# board.net
KiCad netlist of a schematic drawn in EAGLE
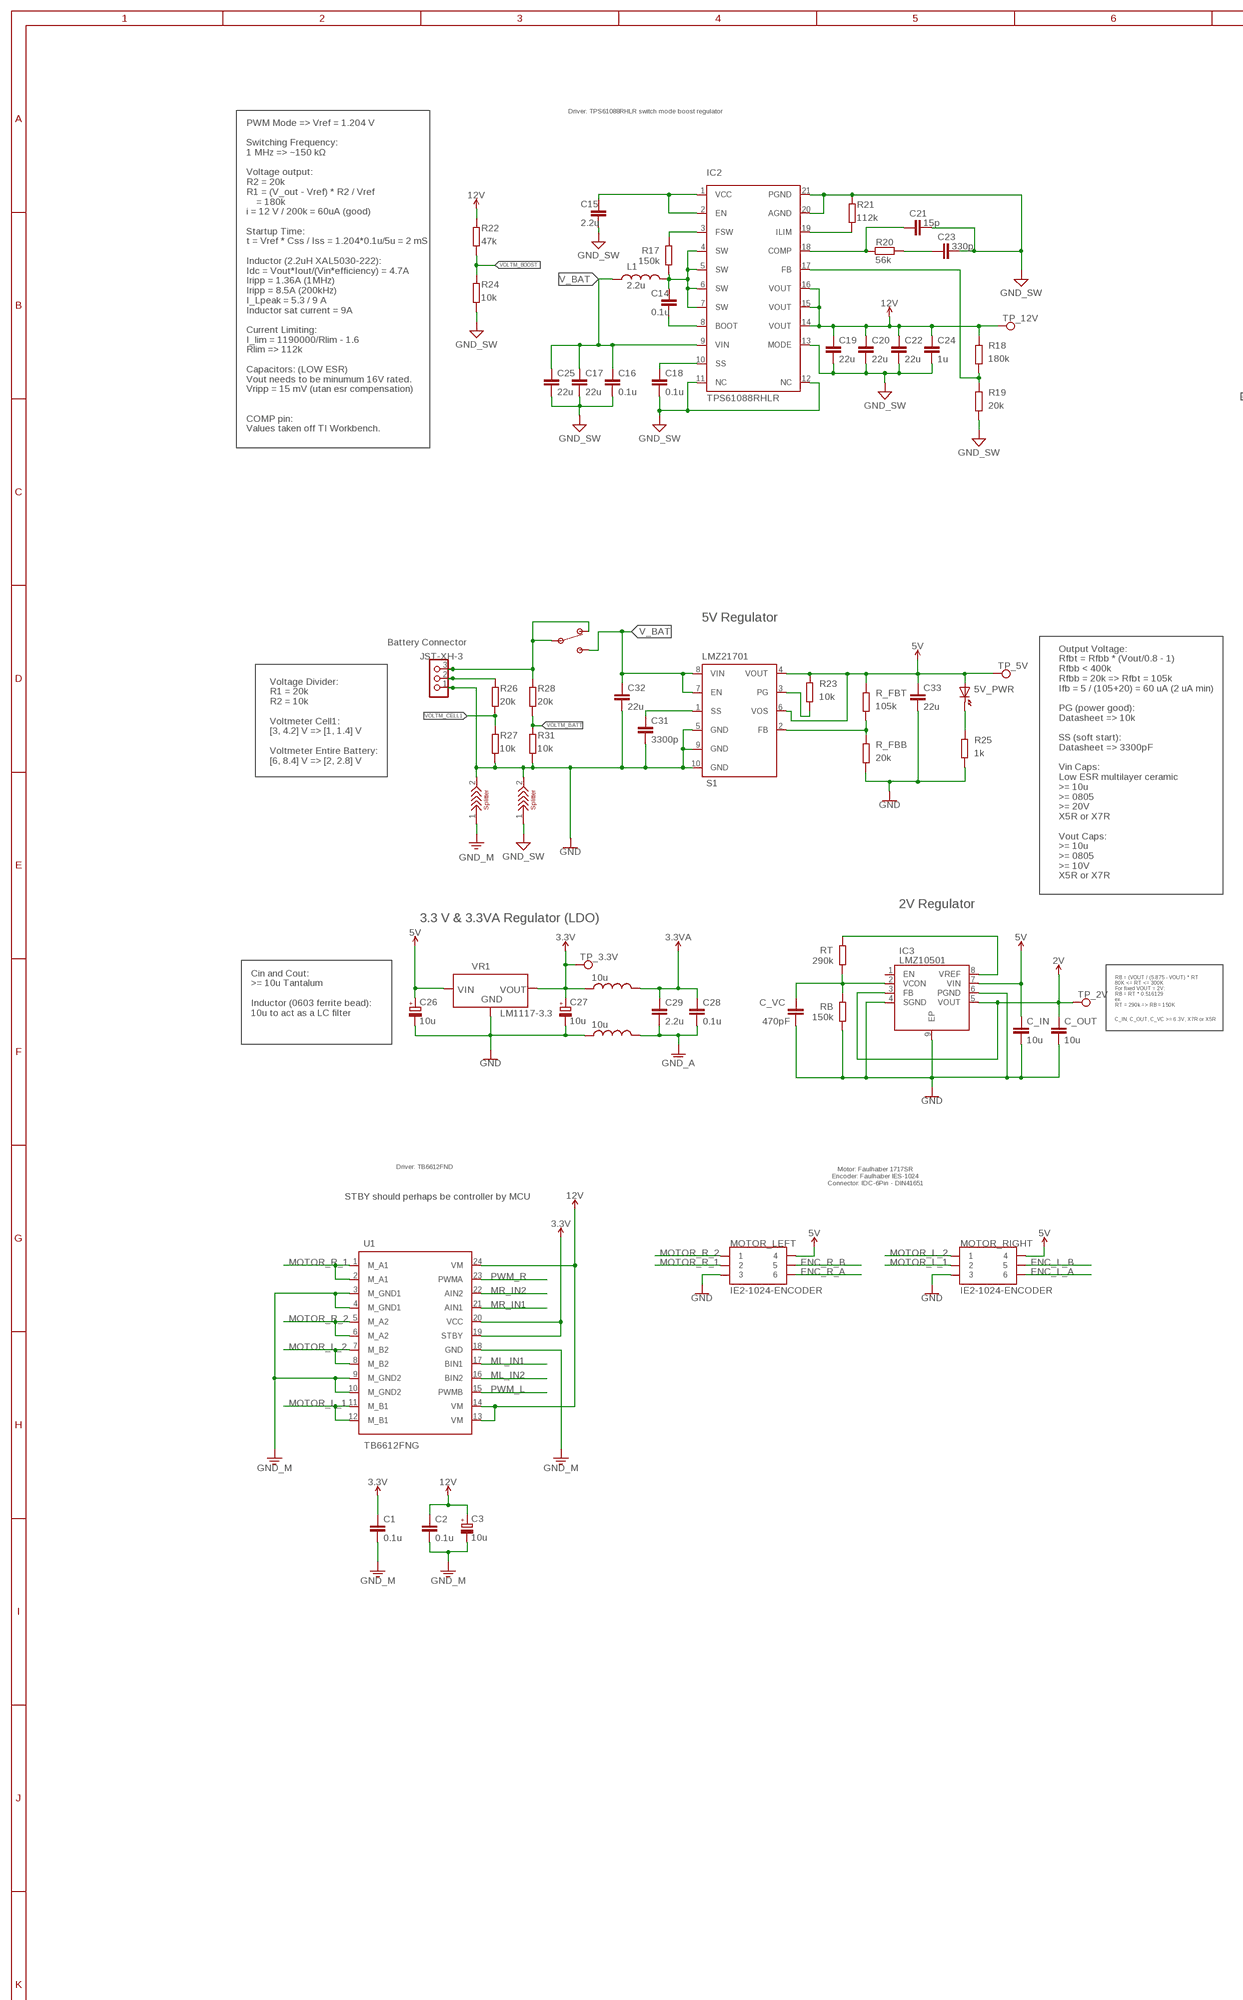
[diagram p0: schematic, sheet 1, part 1 of 3]
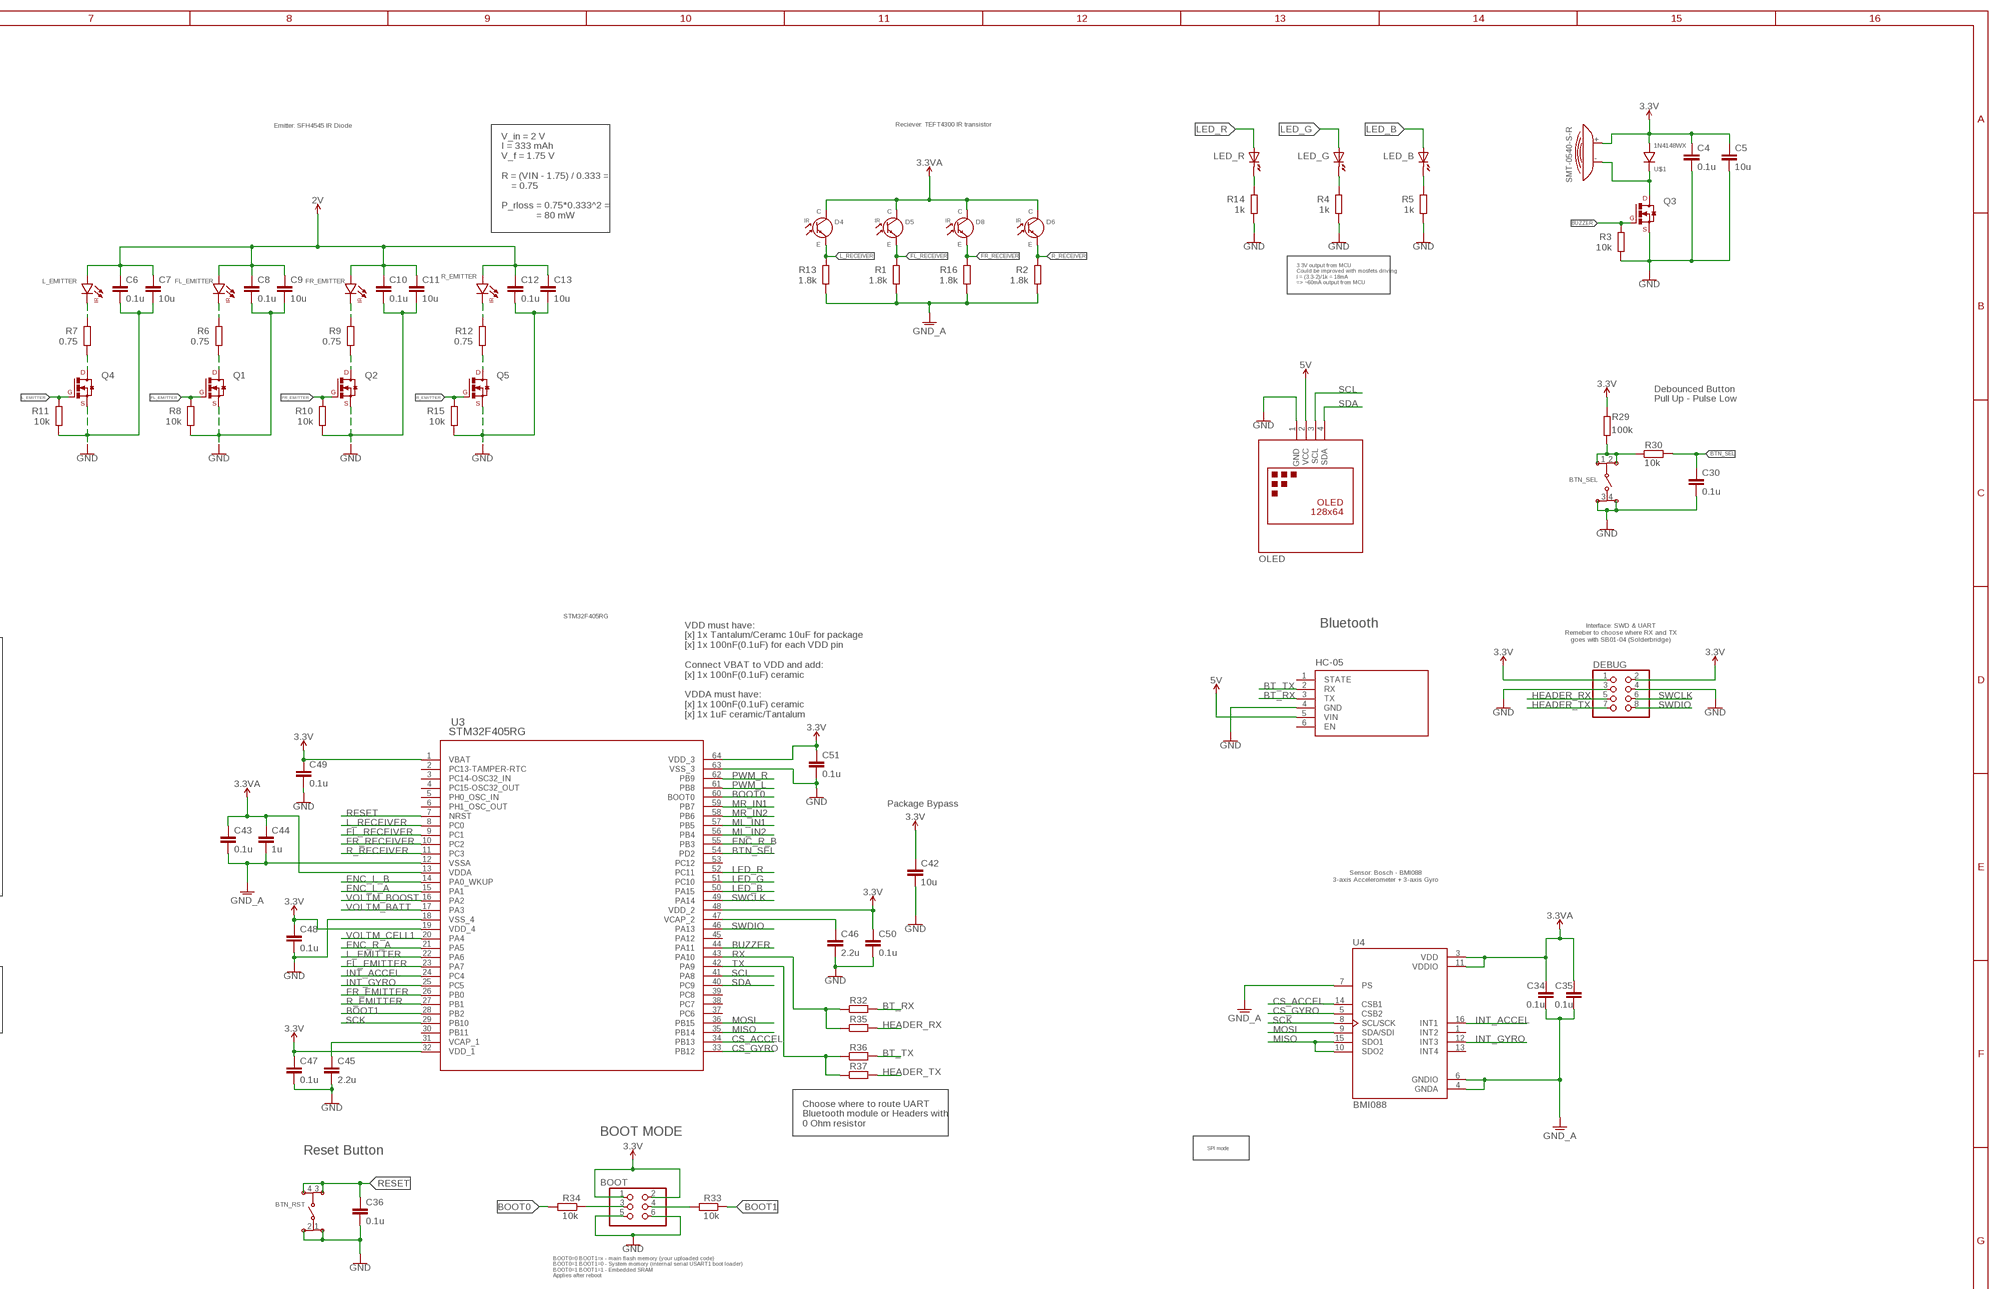
[diagram p1: schematic, sheet 1, part 2 of 3]
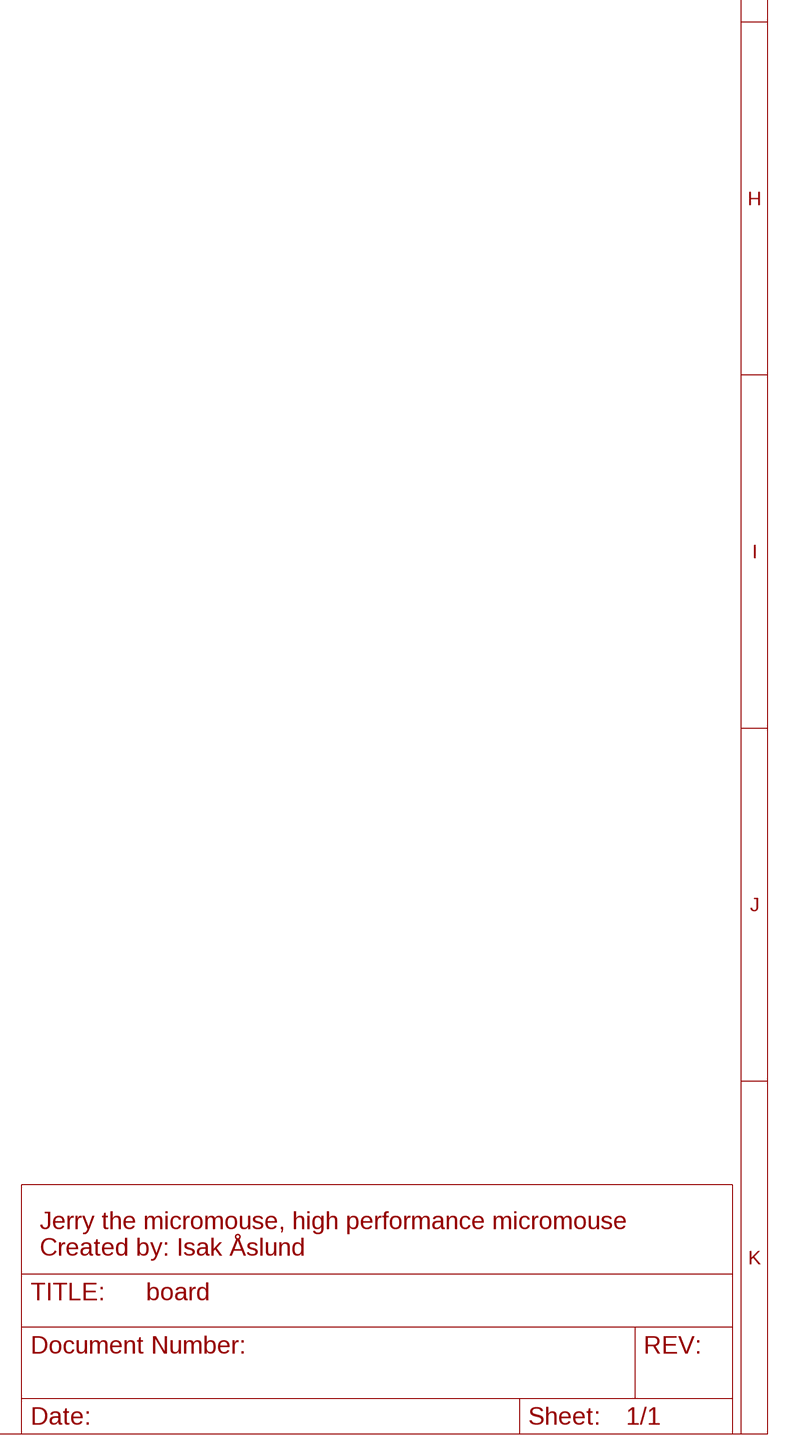
[diagram p2: schematic, sheet 1, part 3 of 3]

(export (version "E")
  (design (tool "Eeschema 10.0.6"))
  (components
    (comp (ref "5V_PWR")
      (value "CHIP-LED0603")
      (footprint "eagle-import:CHIP-LED0603")
      (libsource (lib "eagle-import") (part "CHIP-LED0603"))
    )
    (comp (ref "BOOT")
      (value "PINHD-2X3")
      (footprint "eagle-import:2X03")
      (libsource (lib "eagle-import") (part "PINHD-2X3"))
    )
    (comp (ref "BTN_RST")
      (value "KMR621NGLFS")
      (footprint "eagle-import:KMR621NGLFS")
      (libsource (lib "eagle-import") (part "KMR621NGLFS"))
    )
    (comp (ref "BTN_SEL")
      (value "KMR621NGLFS")
      (footprint "eagle-import:KMR621NGLFS")
      (libsource (lib "eagle-import") (part "KMR621NGLFS"))
    )
    (comp (ref "C1")
      (value "0.1u")
      (footprint "eagle-import:C0603")
      (libsource (lib "eagle-import") (part "C0603"))
    )
    (comp (ref "C2")
      (value "0.1u")
      (footprint "eagle-import:C0603")
      (libsource (lib "eagle-import") (part "C0603"))
    )
    (comp (ref "C3")
      (value "10u")
      (footprint "eagle-import:EIA_6032-28")
      (libsource (lib "eagle-import") (part "KEMET_C"))
    )
    (comp (ref "C4")
      (value "0.1u")
      (footprint "eagle-import:C0603")
      (libsource (lib "eagle-import") (part "C0603"))
    )
    (comp (ref "C5")
      (value "10u")
      (footprint "eagle-import:C0603")
      (libsource (lib "eagle-import") (part "C0603"))
    )
    (comp (ref "C6")
      (value "0.1u")
      (footprint "eagle-import:C0603")
      (libsource (lib "eagle-import") (part "C0603"))
    )
    (comp (ref "C7")
      (value "10u")
      (footprint "eagle-import:C0603")
      (libsource (lib "eagle-import") (part "C0603"))
    )
    (comp (ref "C8")
      (value "0.1u")
      (footprint "eagle-import:C0603")
      (libsource (lib "eagle-import") (part "C0603"))
    )
    (comp (ref "C9")
      (value "10u")
      (footprint "eagle-import:C0603")
      (libsource (lib "eagle-import") (part "C0603"))
    )
    (comp (ref "C10")
      (value "0.1u")
      (footprint "eagle-import:C0603")
      (libsource (lib "eagle-import") (part "C0603"))
    )
    (comp (ref "C11")
      (value "10u")
      (footprint "eagle-import:C0603")
      (libsource (lib "eagle-import") (part "C0603"))
    )
    (comp (ref "C12")
      (value "0.1u")
      (footprint "eagle-import:C0603")
      (libsource (lib "eagle-import") (part "C0603"))
    )
    (comp (ref "C13")
      (value "10u")
      (footprint "eagle-import:C0603")
      (libsource (lib "eagle-import") (part "C0603"))
    )
    (comp (ref "C14")
      (value "0.1u")
      (footprint "eagle-import:C0603")
      (libsource (lib "eagle-import") (part "C0603"))
    )
    (comp (ref "C15")
      (value "2.2u")
      (footprint "eagle-import:C0603")
      (libsource (lib "eagle-import") (part "C0603"))
    )
    (comp (ref "C16")
      (value "0.1u")
      (footprint "eagle-import:C0805")
      (libsource (lib "eagle-import") (part "C0805"))
    )
    (comp (ref "C17")
      (value "22u")
      (footprint "eagle-import:C0805")
      (libsource (lib "eagle-import") (part "C0805"))
    )
    (comp (ref "C18")
      (value "0.1u")
      (footprint "eagle-import:C0603")
      (libsource (lib "eagle-import") (part "C0603"))
    )
    (comp (ref "C19")
      (value "22u")
      (footprint "eagle-import:C0805")
      (libsource (lib "eagle-import") (part "C0805"))
    )
    (comp (ref "C20")
      (value "22u")
      (footprint "eagle-import:C0805")
      (libsource (lib "eagle-import") (part "C0805"))
    )
    (comp (ref "C21")
      (value "15p")
      (footprint "eagle-import:C0603")
      (libsource (lib "eagle-import") (part "C0603"))
    )
    (comp (ref "C22")
      (value "22u")
      (footprint "eagle-import:C0805")
      (libsource (lib "eagle-import") (part "C0805"))
    )
    (comp (ref "C23")
      (value "330p")
      (footprint "eagle-import:C0603")
      (libsource (lib "eagle-import") (part "C0603"))
    )
    (comp (ref "C24")
      (value "1u")
      (footprint "eagle-import:C0805")
      (libsource (lib "eagle-import") (part "C0805"))
    )
    (comp (ref "C25")
      (value "22u")
      (footprint "eagle-import:C0805")
      (libsource (lib "eagle-import") (part "C0805"))
    )
    (comp (ref "C26")
      (value "10u")
      (footprint "eagle-import:SMC_A")
      (libsource (lib "eagle-import") (part "SMC_A"))
    )
    (comp (ref "C27")
      (value "10u")
      (footprint "eagle-import:SMC_A")
      (libsource (lib "eagle-import") (part "SMC_A"))
    )
    (comp (ref "C28")
      (value "0.1u")
      (footprint "eagle-import:C0603")
      (libsource (lib "eagle-import") (part "C0603"))
    )
    (comp (ref "C29")
      (value "2.2u")
      (footprint "eagle-import:C0603")
      (libsource (lib "eagle-import") (part "C0603"))
    )
    (comp (ref "C30")
      (value "0.1u")
      (footprint "eagle-import:C0603")
      (libsource (lib "eagle-import") (part "C0603"))
    )
    (comp (ref "C31")
      (value "3300p")
      (footprint "eagle-import:C0603")
      (libsource (lib "eagle-import") (part "C0603"))
    )
    (comp (ref "C32")
      (value "22u")
      (footprint "eagle-import:C0805")
      (libsource (lib "eagle-import") (part "C0805"))
    )
    (comp (ref "C33")
      (value "22u")
      (footprint "eagle-import:C0805")
      (libsource (lib "eagle-import") (part "C0805"))
    )
    (comp (ref "C34")
      (value "0.1u")
      (footprint "eagle-import:C0603")
      (libsource (lib "eagle-import") (part "C0603"))
    )
    (comp (ref "C35")
      (value "0.1u")
      (footprint "eagle-import:C0603")
      (libsource (lib "eagle-import") (part "C0603"))
    )
    (comp (ref "C36")
      (value "0.1u")
      (footprint "eagle-import:C0603")
      (libsource (lib "eagle-import") (part "C0603"))
    )
    (comp (ref "C42")
      (value "10u")
      (footprint "eagle-import:C0603")
      (libsource (lib "eagle-import") (part "C0603"))
    )
    (comp (ref "C43")
      (value "0.1u")
      (footprint "eagle-import:C0603")
      (libsource (lib "eagle-import") (part "C0603"))
    )
    (comp (ref "C44")
      (value "1u")
      (footprint "eagle-import:C0603")
      (libsource (lib "eagle-import") (part "C0603"))
    )
    (comp (ref "C45")
      (value "2.2u")
      (footprint "eagle-import:C0603")
      (libsource (lib "eagle-import") (part "C0603"))
    )
    (comp (ref "C46")
      (value "2.2u")
      (footprint "eagle-import:C0603")
      (libsource (lib "eagle-import") (part "C0603"))
    )
    (comp (ref "C47")
      (value "0.1u")
      (footprint "eagle-import:C0603")
      (libsource (lib "eagle-import") (part "C0603"))
    )
    (comp (ref "C48")
      (value "0.1u")
      (footprint "eagle-import:C0603")
      (libsource (lib "eagle-import") (part "C0603"))
    )
    (comp (ref "C49")
      (value "0.1u")
      (footprint "eagle-import:C0603")
      (libsource (lib "eagle-import") (part "C0603"))
    )
    (comp (ref "C50")
      (value "0.1u")
      (footprint "eagle-import:C0603")
      (libsource (lib "eagle-import") (part "C0603"))
    )
    (comp (ref "C51")
      (value "0.1u")
      (footprint "eagle-import:C0603")
      (libsource (lib "eagle-import") (part "C0603"))
    )
    (comp (ref "C_IN")
      (value "10u")
      (footprint "eagle-import:C0805")
      (libsource (lib "eagle-import") (part "C0805"))
    )
    (comp (ref "C_OUT")
      (value "10u")
      (footprint "eagle-import:C0805")
      (libsource (lib "eagle-import") (part "C0805"))
    )
    (comp (ref "C_VC")
      (value "470pF")
      (footprint "eagle-import:C0603")
      (libsource (lib "eagle-import") (part "C0603"))
    )
    (comp (ref "D4")
      (value "TEFT4300")
      (footprint "eagle-import:3MM_PHOTOTRANSISTOR")
      (libsource (lib "eagle-import") (part "TEFT4300"))
    )
    (comp (ref "D5")
      (value "TEFT4300")
      (footprint "eagle-import:3MM_PHOTOTRANSISTOR")
      (libsource (lib "eagle-import") (part "TEFT4300"))
    )
    (comp (ref "D6")
      (value "TEFT4300")
      (footprint "eagle-import:3MM_PHOTOTRANSISTOR")
      (libsource (lib "eagle-import") (part "TEFT4300"))
    )
    (comp (ref "D8")
      (value "TEFT4300")
      (footprint "eagle-import:3MM_PHOTOTRANSISTOR")
      (libsource (lib "eagle-import") (part "TEFT4300"))
    )
    (comp (ref "DEBUG")
      (value "PINHD-2X4")
      (footprint "eagle-import:2X04")
      (libsource (lib "eagle-import") (part "PINHD-2X4"))
    )
    (comp (ref "FL_EMITTER")
      (value "SFH_4545")
      (footprint "eagle-import:SFH_4545")
      (libsource (lib "eagle-import") (part "SFH_4545"))
    )
    (comp (ref "FP1")
      (value "10u")
      (footprint "eagle-import:R0805")
      (libsource (lib "eagle-import") (part "WE-CBF_0805"))
    )
    (comp (ref "FP2")
      (value "10u")
      (footprint "eagle-import:R0805")
      (libsource (lib "eagle-import") (part "WE-CBF_0805"))
    )
    (comp (ref "FR_EMITTER")
      (value "SFH_4545")
      (footprint "eagle-import:SFH_4545")
      (libsource (lib "eagle-import") (part "SFH_4545"))
    )
    (comp (ref "HC-05")
      (value "WIRELESS-BLUETOOTH-HC-05")
      (footprint "eagle-import:WIRELESS-BLUETOOTH-HC-05")
      (libsource (lib "eagle-import") (part "WIRELESS-BLUETOOTH-HC-05"))
    )
    (comp (ref "IC2")
      (value "TPS61088RHLR")
      (footprint "eagle-import:RHL(R-PVQFN-N20)_1")
      (fields (field (name "MOUSER_PART_NUMBER") "595-TPS61088RHLR"))
      (libsource (lib "eagle-import") (part "TPS61088RHLR"))
    )
    (comp (ref "IC3")
      (value "LMZ10501")
      (footprint "eagle-import:SON65P260X300X150-9N")
      (fields
        (field (name "MANUFACTURER_PART_NUMBER") "LMZ10501SILT")
        (field (name "MOUSER_PART_NUMBER") "595-LMZ10501SILT")
      )
      (libsource (lib "eagle-import") (part "LMZ10501"))
    )
    (comp (ref "L1")
      (value "2.2u")
      (footprint "eagle-import:XAL5030")
      (fields
        (field (name "MANUFACTURER_PART_NUMBER") "XAL5030-222MEC")
        (field (name "MOUSER_PART_NUMBER") "994-XAL5030-222MEC")
      )
      (libsource (lib "eagle-import") (part "XAL5030-222MEC"))
    )
    (comp (ref "LED_B")
      (value "CHIP-LED0603")
      (footprint "eagle-import:CHIP-LED0603")
      (libsource (lib "eagle-import") (part "CHIP-LED0603"))
    )
    (comp (ref "LED_G")
      (value "CHIP-LED0603")
      (footprint "eagle-import:CHIP-LED0603")
      (libsource (lib "eagle-import") (part "CHIP-LED0603"))
    )
    (comp (ref "LED_R")
      (value "CHIP-LED0603")
      (footprint "eagle-import:CHIP-LED0603")
      (libsource (lib "eagle-import") (part "CHIP-LED0603"))
    )
    (comp (ref "L_EMITTER")
      (value "SFH_4545")
      (footprint "eagle-import:SFH_4545")
      (libsource (lib "eagle-import") (part "SFH_4545"))
    )
    (comp (ref "MOTOR_LEFT")
      (value "IE2-1024-ENCODER")
      (footprint "eagle-import:IE2-1024-ENCODER")
      (libsource (lib "eagle-import") (part "IE2-1024-ENCODER"))
    )
    (comp (ref "MOTOR_RIGHT")
      (value "IE2-1024-ENCODER")
      (footprint "eagle-import:IE2-1024-ENCODER")
      (libsource (lib "eagle-import") (part "IE2-1024-ENCODER"))
    )
    (comp (ref "OLED")
      (value "DISPLAY-OLED-128X64-I2C")
      (footprint "eagle-import:DISPLAY-OLED-128X64-I2C")
      (libsource (lib "eagle-import") (part "DISPLAY-OLED-128X64-I2C"))
    )
    (comp (ref "Q1")
      (value "IRFML8244TRPBF")
      (footprint "eagle-import:SOT95P235X110-3")
      (libsource (lib "eagle-import") (part "IRFML8244TRPBF"))
    )
    (comp (ref "Q2")
      (value "IRFML8244TRPBF")
      (footprint "eagle-import:SOT95P235X110-3")
      (libsource (lib "eagle-import") (part "IRFML8244TRPBF"))
    )
    (comp (ref "Q3")
      (value "IRFML8244TRPBF")
      (footprint "eagle-import:SOT95P235X110-3")
      (libsource (lib "eagle-import") (part "IRFML8244TRPBF"))
    )
    (comp (ref "Q4")
      (value "IRFML8244TRPBF")
      (footprint "eagle-import:SOT95P235X110-3")
      (libsource (lib "eagle-import") (part "IRFML8244TRPBF"))
    )
    (comp (ref "Q5")
      (value "IRFML8244TRPBF")
      (footprint "eagle-import:SOT95P235X110-3")
      (libsource (lib "eagle-import") (part "IRFML8244TRPBF"))
    )
    (comp (ref "R1")
      (value "1.8k")
      (footprint "eagle-import:R0603")
      (libsource (lib "eagle-import") (part "R0603"))
    )
    (comp (ref "R2")
      (value "1.8k")
      (footprint "eagle-import:R0603")
      (libsource (lib "eagle-import") (part "R0603"))
    )
    (comp (ref "R3")
      (value "10k")
      (footprint "eagle-import:R0603")
      (libsource (lib "eagle-import") (part "R0603"))
    )
    (comp (ref "R4")
      (value "1k")
      (footprint "eagle-import:R0603")
      (libsource (lib "eagle-import") (part "R0603"))
    )
    (comp (ref "R5")
      (value "1k")
      (footprint "eagle-import:R0603")
      (libsource (lib "eagle-import") (part "R0603"))
    )
    (comp (ref "R6")
      (value "0.75")
      (footprint "eagle-import:R0603")
      (libsource (lib "eagle-import") (part "R0603"))
    )
    (comp (ref "R7")
      (value "0.75")
      (footprint "eagle-import:R0603")
      (libsource (lib "eagle-import") (part "R0603"))
    )
    (comp (ref "R8")
      (value "10k")
      (footprint "eagle-import:R0603")
      (libsource (lib "eagle-import") (part "R0603"))
    )
    (comp (ref "R9")
      (value "0.75")
      (footprint "eagle-import:R0603")
      (libsource (lib "eagle-import") (part "R0603"))
    )
    (comp (ref "R10")
      (value "10k")
      (footprint "eagle-import:R0603")
      (libsource (lib "eagle-import") (part "R0603"))
    )
    (comp (ref "R11")
      (value "10k")
      (footprint "eagle-import:R0603")
      (libsource (lib "eagle-import") (part "R0603"))
    )
    (comp (ref "R12")
      (value "0.75")
      (footprint "eagle-import:R0603")
      (libsource (lib "eagle-import") (part "R0603"))
    )
    (comp (ref "R13")
      (value "1.8k")
      (footprint "eagle-import:R0603")
      (libsource (lib "eagle-import") (part "R0603"))
    )
    (comp (ref "R14")
      (value "1k")
      (footprint "eagle-import:R0603")
      (libsource (lib "eagle-import") (part "R0603"))
    )
    (comp (ref "R15")
      (value "10k")
      (footprint "eagle-import:R0603")
      (libsource (lib "eagle-import") (part "R0603"))
    )
    (comp (ref "R16")
      (value "1.8k")
      (footprint "eagle-import:R0603")
      (libsource (lib "eagle-import") (part "R0603"))
    )
    (comp (ref "R17")
      (value "150k")
      (footprint "eagle-import:R0603")
      (libsource (lib "eagle-import") (part "R0603"))
    )
    (comp (ref "R18")
      (value "180k")
      (footprint "eagle-import:R0603")
      (libsource (lib "eagle-import") (part "R0603"))
    )
    (comp (ref "R19")
      (value "20k")
      (footprint "eagle-import:R0603")
      (libsource (lib "eagle-import") (part "R0603"))
    )
    (comp (ref "R20")
      (value "56k")
      (footprint "eagle-import:R0603")
      (libsource (lib "eagle-import") (part "R0603"))
    )
    (comp (ref "R21")
      (value "112k")
      (footprint "eagle-import:R0603")
      (libsource (lib "eagle-import") (part "R0603"))
    )
    (comp (ref "R22")
      (value "47k")
      (footprint "eagle-import:R0603")
      (libsource (lib "eagle-import") (part "R0603"))
    )
    (comp (ref "R23")
      (value "10k")
      (footprint "eagle-import:R0603")
      (fields (field (name "TOLERANCE") "1%"))
      (libsource (lib "eagle-import") (part "R0603"))
    )
    (comp (ref "R24")
      (value "10k")
      (footprint "eagle-import:R0603")
      (libsource (lib "eagle-import") (part "R0603"))
    )
    (comp (ref "R25")
      (value "1k")
      (footprint "eagle-import:R0603")
      (libsource (lib "eagle-import") (part "R0603"))
    )
    (comp (ref "R26")
      (value "20k")
      (footprint "eagle-import:R0603")
      (libsource (lib "eagle-import") (part "R0603"))
    )
    (comp (ref "R27")
      (value "10k")
      (footprint "eagle-import:R0603")
      (libsource (lib "eagle-import") (part "R0603"))
    )
    (comp (ref "R28")
      (value "20k")
      (footprint "eagle-import:R0603")
      (libsource (lib "eagle-import") (part "R0603"))
    )
    (comp (ref "R29")
      (value "100k")
      (footprint "eagle-import:R0603")
      (libsource (lib "eagle-import") (part "R0603"))
    )
    (comp (ref "R30")
      (value "10k")
      (footprint "eagle-import:R0603")
      (libsource (lib "eagle-import") (part "R0603"))
    )
    (comp (ref "R31")
      (value "10k")
      (footprint "eagle-import:R0603")
      (libsource (lib "eagle-import") (part "R0603"))
    )
    (comp (ref "R32")
      (value "0")
      (footprint "eagle-import:R0603")
      (libsource (lib "eagle-import") (part "R0603"))
    )
    (comp (ref "R33")
      (value "10k")
      (footprint "eagle-import:R0603")
      (libsource (lib "eagle-import") (part "R0603"))
    )
    (comp (ref "R34")
      (value "10k")
      (footprint "eagle-import:R0603")
      (libsource (lib "eagle-import") (part "R0603"))
    )
    (comp (ref "R35")
      (value "0")
      (footprint "eagle-import:R0603")
      (libsource (lib "eagle-import") (part "R0603"))
    )
    (comp (ref "R36")
      (value "0")
      (footprint "eagle-import:R0603")
      (libsource (lib "eagle-import") (part "R0603"))
    )
    (comp (ref "R37")
      (value "0")
      (footprint "eagle-import:R0603")
      (libsource (lib "eagle-import") (part "R0603"))
    )
    (comp (ref "RB")
      (value "150k")
      (footprint "eagle-import:R0603")
      (libsource (lib "eagle-import") (part "R0603"))
    )
    (comp (ref "RT")
      (value "290k")
      (footprint "eagle-import:R0603")
      (fields (field (name "TOLERANCE") "1%"))
      (libsource (lib "eagle-import") (part "R0603"))
    )
    (comp (ref "R_EMITTER")
      (value "SFH_4545")
      (footprint "eagle-import:SFH_4545")
      (libsource (lib "eagle-import") (part "SFH_4545"))
    )
    (comp (ref "R_FBB")
      (value "20k")
      (footprint "eagle-import:R0603")
      (libsource (lib "eagle-import") (part "R0603"))
    )
    (comp (ref "R_FBT")
      (value "105k")
      (footprint "eagle-import:R0603")
      (libsource (lib "eagle-import") (part "R0603"))
    )
    (comp (ref "S1")
      (value "LMZ21701")
      (footprint "eagle-import:LMZ21701")
      (fields
        (field (name "MANUFACTURER_PART_NUMBER") "LMZ21701SILR")
        (field (name "MOUSER_PART_NUMBER") "595-LMZ21701SILR")
      )
      (libsource (lib "eagle-import") (part "LMZ21701"))
    )
    (comp (ref "SW")
      (value "SPDT-500SSP1S1M6QEA")
      (footprint "eagle-import:500SSP1S1M6QEA")
      (libsource (lib "eagle-import") (part "SPDT-500SSP1S1M6QEA"))
    )
    (comp (ref "TP_2V")
      (value "TEST-POINT3X5")
      (footprint "eagle-import:PAD.03X.05")
      (libsource (lib "eagle-import") (part "TEST-POINT3X5"))
    )
    (comp (ref "TP_3.3V")
      (value "TEST-POINT3X5")
      (footprint "eagle-import:PAD.03X.05")
      (libsource (lib "eagle-import") (part "TEST-POINT3X5"))
    )
    (comp (ref "TP_5V")
      (value "TEST-POINT3X5")
      (footprint "eagle-import:PAD.03X.05")
      (libsource (lib "eagle-import") (part "TEST-POINT3X5"))
    )
    (comp (ref "TP_12V")
      (value "TEST-POINT3X5")
      (footprint "eagle-import:PAD.03X.05")
      (libsource (lib "eagle-import") (part "TEST-POINT3X5"))
    )
    (comp (ref "U$1")
      (value "1N4148WX")
      (footprint "eagle-import:1N4148WX_SOD-323-2")
      (libsource (lib "eagle-import") (part "DIODE_1N4148WX"))
    )
    (comp (ref "U$4")
      (value "SMT-0540-S-R")
      (footprint "eagle-import:SMT-0540-S-R")
      (libsource (lib "eagle-import") (part "SMT-0540-S-R"))
    )
    (comp (ref "U$6")
      (value "SPLITTER")
      (footprint "eagle-import:SPLITTER")
      (libsource (lib "eagle-import") (part "SPLITTER"))
    )
    (comp (ref "U$7")
      (value "SPLITTER")
      (footprint "eagle-import:SPLITTER")
      (libsource (lib "eagle-import") (part "SPLITTER"))
    )
    (comp (ref "U$10")
      (value "JST-XH-3")
      (footprint "eagle-import:JST-XH-03")
      (libsource (lib "eagle-import") (part "JST-XH-3"))
    )
    (comp (ref "U1")
      (value "TB6612FNG")
      (footprint "eagle-import:SOP65P760X160-24")
      (libsource (lib "eagle-import") (part "TB6612FNG"))
    )
    (comp (ref "U3")
      (value "STM32F405RG")
      (footprint "eagle-import:LQFP-64")
      (libsource (lib "eagle-import") (part "STM32F405RG"))
    )
    (comp (ref "U4")
      (value "BMI088")
      (footprint "eagle-import:PQFN50P450X300X100-16N")
      (fields (field (name "MF") "Bosch Sensortec"))
      (libsource (lib "eagle-import") (part "BMI088"))
    )
    (comp (ref "VR1")
      (value "LM1117-3.3")
      (footprint "eagle-import:SOT230P700X180-4")
      (libsource (lib "eagle-import") (part "LM1117-3.3"))
    )
  )
  (nets
    (net (code "1") (name "/BT_RX") (class "Default")
      (node (ref "HC-05") (pin "3") (pinfunction "TX_3") (pintype "output"))
      (node (ref "R32") (pin "2") (pinfunction "2_2") (pintype "passive"))
    )
    (net (code "2") (name "/BT_TX") (class "Default")
      (node (ref "HC-05") (pin "2") (pinfunction "RX_2") (pintype "input"))
      (node (ref "R36") (pin "2") (pinfunction "2_2") (pintype "passive"))
    )
    (net (code "3") (name "/CS_ACCEL") (class "Default")
      (node (ref "U3") (pin "34") (pinfunction "PB13_34") (pintype "bidirectional"))
      (node (ref "U4") (pin "14") (pinfunction "CSB1_14") (pintype "input"))
    )
    (net (code "4") (name "/CS_GYRO") (class "Default")
      (node (ref "U3") (pin "33") (pinfunction "PB12_33") (pintype "bidirectional"))
      (node (ref "U4") (pin "5") (pinfunction "CSB2_5") (pintype "input"))
    )
    (net (code "5") (name "/ENC_L_A") (class "Default")
      (node (ref "MOTOR_RIGHT") (pin "6") (pinfunction "6_6") (pintype "bidirectional"))
      (node (ref "U3") (pin "15") (pinfunction "PA1_15") (pintype "bidirectional"))
    )
    (net (code "6") (name "/ENC_L_B") (class "Default")
      (node (ref "MOTOR_RIGHT") (pin "5") (pinfunction "5_5") (pintype "bidirectional"))
      (node (ref "U3") (pin "14") (pinfunction "PA0_WKUP_14") (pintype "bidirectional"))
    )
    (net (code "7") (name "/ENC_R_A") (class "Default")
      (node (ref "MOTOR_LEFT") (pin "6") (pinfunction "6_6") (pintype "bidirectional"))
      (node (ref "U3") (pin "21") (pinfunction "PA5_21") (pintype "bidirectional"))
    )
    (net (code "8") (name "/ENC_R_B") (class "Default")
      (node (ref "MOTOR_LEFT") (pin "5") (pinfunction "5_5") (pintype "bidirectional"))
      (node (ref "U3") (pin "55") (pinfunction "PB3_55") (pintype "bidirectional"))
    )
    (net (code "9") (name "/HEADER_RX") (class "Default")
      (node (ref "DEBUG") (pin "5") (pinfunction "5_5") (pintype "passive"))
      (node (ref "R35") (pin "2") (pinfunction "2_2") (pintype "passive"))
    )
    (net (code "10") (name "/HEADER_TX") (class "Default")
      (node (ref "DEBUG") (pin "7") (pinfunction "7_7") (pintype "passive"))
      (node (ref "R37") (pin "2") (pinfunction "2_2") (pintype "passive"))
    )
    (net (code "11") (name "/INT_ACCEL") (class "Default")
      (node (ref "U3") (pin "24") (pinfunction "PC4_24") (pintype "bidirectional"))
      (node (ref "U4") (pin "16") (pinfunction "INT1_16") (pintype "bidirectional"))
    )
    (net (code "12") (name "/INT_GYRO") (class "Default")
      (node (ref "U3") (pin "25") (pinfunction "PC5_25") (pintype "bidirectional"))
      (node (ref "U4") (pin "12") (pinfunction "INT3_12") (pintype "bidirectional"))
    )
    (net (code "13") (name "/MISO") (class "Default")
      (node (ref "U3") (pin "35") (pinfunction "PB14_35") (pintype "bidirectional"))
      (node (ref "U4") (pin "10") (pinfunction "SDO2_10") (pintype "output"))
      (node (ref "U4") (pin "15") (pinfunction "SDO1_15") (pintype "output"))
    )
    (net (code "14") (name "/ML_IN1") (class "Default")
      (node (ref "U1") (pin "17") (pinfunction "BIN1_17") (pintype "input"))
      (node (ref "U3") (pin "57") (pinfunction "PB5_57") (pintype "bidirectional"))
    )
    (net (code "15") (name "/ML_IN2") (class "Default")
      (node (ref "U1") (pin "16") (pinfunction "BIN2_16") (pintype "input"))
      (node (ref "U3") (pin "56") (pinfunction "PB4_56") (pintype "bidirectional"))
    )
    (net (code "16") (name "/MOSI") (class "Default")
      (node (ref "U3") (pin "36") (pinfunction "PB15_36") (pintype "bidirectional"))
      (node (ref "U4") (pin "9") (pinfunction "SDA/SDI_9") (pintype "bidirectional"))
    )
    (net (code "17") (name "/MOTOR_L_1") (class "Default")
      (node (ref "MOTOR_RIGHT") (pin "2") (pinfunction "2_2") (pintype "bidirectional"))
      (node (ref "U1") (pin "11") (pinfunction "M_B1_11") (pintype "bidirectional"))
      (node (ref "U1") (pin "12") (pinfunction "M_B1_12") (pintype "bidirectional"))
    )
    (net (code "18") (name "/MOTOR_L_2") (class "Default")
      (node (ref "MOTOR_RIGHT") (pin "1") (pinfunction "1_1") (pintype "bidirectional"))
      (node (ref "U1") (pin "7") (pinfunction "M_B2_7") (pintype "bidirectional"))
      (node (ref "U1") (pin "8") (pinfunction "M_B2_8") (pintype "bidirectional"))
    )
    (net (code "19") (name "/MOTOR_R_1") (class "Default")
      (node (ref "MOTOR_LEFT") (pin "2") (pinfunction "2_2") (pintype "bidirectional"))
      (node (ref "U1") (pin "1") (pinfunction "M_A1_1") (pintype "bidirectional"))
      (node (ref "U1") (pin "2") (pinfunction "M_A1_2") (pintype "bidirectional"))
    )
    (net (code "20") (name "/MOTOR_R_2") (class "Default")
      (node (ref "MOTOR_LEFT") (pin "1") (pinfunction "1_1") (pintype "bidirectional"))
      (node (ref "U1") (pin "5") (pinfunction "M_A2_5") (pintype "bidirectional"))
      (node (ref "U1") (pin "6") (pinfunction "M_A2_6") (pintype "bidirectional"))
    )
    (net (code "21") (name "/MR_IN1") (class "Default")
      (node (ref "U1") (pin "21") (pinfunction "AIN1_21") (pintype "input"))
      (node (ref "U3") (pin "59") (pinfunction "PB7_59") (pintype "bidirectional"))
    )
    (net (code "22") (name "/MR_IN2") (class "Default")
      (node (ref "U1") (pin "22") (pinfunction "AIN2_22") (pintype "input"))
      (node (ref "U3") (pin "58") (pinfunction "PB6_58") (pintype "bidirectional"))
    )
    (net (code "23") (name "/PWM_L") (class "Default")
      (node (ref "U1") (pin "15") (pinfunction "PWMB_15") (pintype "input"))
      (node (ref "U3") (pin "61") (pinfunction "PB8_61") (pintype "bidirectional"))
    )
    (net (code "24") (name "/PWM_R") (class "Default")
      (node (ref "U1") (pin "23") (pinfunction "PWMA_23") (pintype "input"))
      (node (ref "U3") (pin "62") (pinfunction "PB9_62") (pintype "bidirectional"))
    )
    (net (code "25") (name "/RX") (class "Default")
      (node (ref "R32") (pin "1") (pinfunction "1_1") (pintype "passive"))
      (node (ref "R35") (pin "1") (pinfunction "1_1") (pintype "passive"))
      (node (ref "U3") (pin "43") (pinfunction "PA10_43") (pintype "bidirectional"))
    )
    (net (code "26") (name "/SCK") (class "Default")
      (node (ref "U3") (pin "29") (pinfunction "PB10_29") (pintype "bidirectional"))
      (node (ref "U4") (pin "8") (pinfunction "SCL/SCK_8") (pintype "input"))
    )
    (net (code "27") (name "/SCL") (class "Default")
      (node (ref "OLED") (pin "3") (pinfunction "SCL_3") (pintype "bidirectional"))
      (node (ref "U3") (pin "41") (pinfunction "PA8_41") (pintype "bidirectional"))
    )
    (net (code "28") (name "/SDA") (class "Default")
      (node (ref "OLED") (pin "4") (pinfunction "SDA_4") (pintype "bidirectional"))
      (node (ref "U3") (pin "40") (pinfunction "PC9_40") (pintype "bidirectional"))
    )
    (net (code "29") (name "/SWCLK") (class "Default")
      (node (ref "DEBUG") (pin "6") (pinfunction "6_6") (pintype "passive"))
      (node (ref "U3") (pin "49") (pinfunction "PA14_49") (pintype "bidirectional"))
    )
    (net (code "30") (name "/SWDIO") (class "Default")
      (node (ref "DEBUG") (pin "8") (pinfunction "8_8") (pintype "passive"))
      (node (ref "U3") (pin "46") (pinfunction "PA13_46") (pintype "bidirectional"))
    )
    (net (code "31") (name "/TX") (class "Default")
      (node (ref "R36") (pin "1") (pinfunction "1_1") (pintype "passive"))
      (node (ref "R37") (pin "1") (pinfunction "1_1") (pintype "passive"))
      (node (ref "U3") (pin "42") (pinfunction "PA9_42") (pintype "bidirectional"))
    )
    (net (code "32") (name "2V") (class "Default")
      (node (ref "C10") (pin "1") (pinfunction "1_1") (pintype "passive"))
      (node (ref "C11") (pin "1") (pinfunction "1_1") (pintype "passive"))
      (node (ref "C12") (pin "1") (pinfunction "1_1") (pintype "passive"))
      (node (ref "C13") (pin "1") (pinfunction "1_1") (pintype "passive"))
      (node (ref "C6") (pin "1") (pinfunction "1_1") (pintype "passive"))
      (node (ref "C7") (pin "1") (pinfunction "1_1") (pintype "passive"))
      (node (ref "C8") (pin "1") (pinfunction "1_1") (pintype "passive"))
      (node (ref "C9") (pin "1") (pinfunction "1_1") (pintype "passive"))
      (node (ref "C_OUT") (pin "1") (pinfunction "1_1") (pintype "passive"))
      (node (ref "FL_EMITTER") (pin "+") (pinfunction "+_ANODE_+") (pintype "passive"))
      (node (ref "FR_EMITTER") (pin "+") (pinfunction "+_ANODE_+") (pintype "passive"))
      (node (ref "IC3") (pin "3") (pinfunction "FB_3") (pintype "input"))
      (node (ref "IC3") (pin "5") (pinfunction "VOUT_5") (pintype "power_in"))
      (node (ref "L_EMITTER") (pin "+") (pinfunction "+_ANODE_+") (pintype "passive"))
      (node (ref "R_EMITTER") (pin "+") (pinfunction "+_ANODE_+") (pintype "passive"))
      (node (ref "TP_2V") (pin "P$1") (pinfunction "1_P$1") (pintype "bidirectional"))
    )
    (net (code "33") (name "3.3V") (class "Default")
      (node (ref "BOOT") (pin "1") (pinfunction "1_1") (pintype "passive"))
      (node (ref "BOOT") (pin "2") (pinfunction "2_2") (pintype "passive"))
      (node (ref "C1") (pin "1") (pinfunction "1_1") (pintype "passive"))
      (node (ref "C27") (pin "+") (pinfunction "+_+") (pintype "passive"))
      (node (ref "C4") (pin "1") (pinfunction "1_1") (pintype "passive"))
      (node (ref "C42") (pin "1") (pinfunction "1_1") (pintype "passive"))
      (node (ref "C47") (pin "1") (pinfunction "1_1") (pintype "passive"))
      (node (ref "C48") (pin "1") (pinfunction "1_1") (pintype "passive"))
      (node (ref "C49") (pin "1") (pinfunction "1_1") (pintype "passive"))
      (node (ref "C5") (pin "1") (pinfunction "1_1") (pintype "passive"))
      (node (ref "C50") (pin "1") (pinfunction "1_1") (pintype "passive"))
      (node (ref "C51") (pin "1") (pinfunction "1_1") (pintype "passive"))
      (node (ref "DEBUG") (pin "1") (pinfunction "1_1") (pintype "passive"))
      (node (ref "DEBUG") (pin "2") (pinfunction "2_2") (pintype "passive"))
      (node (ref "FP1") (pin "1") (pinfunction "1_1") (pintype "passive"))
      (node (ref "R29") (pin "1") (pinfunction "1_1") (pintype "passive"))
      (node (ref "TP_3.3V") (pin "P$1") (pinfunction "1_P$1") (pintype "bidirectional"))
      (node (ref "U$1") (pin "+") (pinfunction "+_ANODE_+") (pintype "passive"))
      (node (ref "U$4") (pin "+") (pinfunction "+_+") (pintype "bidirectional"))
      (node (ref "U1") (pin "19") (pinfunction "STBY_19") (pintype "input"))
      (node (ref "U1") (pin "20") (pinfunction "VCC_20") (pintype "power_in"))
      (node (ref "U3") (pin "1") (pinfunction "VBAT_1") (pintype "power_in"))
      (node (ref "U3") (pin "19") (pinfunction "VDD_4_19") (pintype "power_in"))
      (node (ref "U3") (pin "32") (pinfunction "VDD_1_32") (pintype "power_in"))
      (node (ref "U3") (pin "48") (pinfunction "VDD_2_48") (pintype "power_in"))
      (node (ref "U3") (pin "64") (pinfunction "VDD_3_64") (pintype "power_in"))
      (node (ref "VR1") (pin "2") (pinfunction "VOUT_2") (pintype "power_in"))
      (node (ref "VR1") (pin "4") (pinfunction "VOUT_4") (pintype "power_in"))
    )
    (net (code "34") (name "3.3VA") (class "Default")
      (node (ref "C28") (pin "1") (pinfunction "1_1") (pintype "passive"))
      (node (ref "C29") (pin "1") (pinfunction "1_1") (pintype "passive"))
      (node (ref "C34") (pin "1") (pinfunction "1_1") (pintype "passive"))
      (node (ref "C35") (pin "1") (pinfunction "1_1") (pintype "passive"))
      (node (ref "C43") (pin "1") (pinfunction "1_1") (pintype "passive"))
      (node (ref "C44") (pin "1") (pinfunction "1_1") (pintype "passive"))
      (node (ref "D4") (pin "C") (pinfunction "C_+_C") (pintype "input"))
      (node (ref "D5") (pin "C") (pinfunction "C_+_C") (pintype "input"))
      (node (ref "D6") (pin "C") (pinfunction "C_+_C") (pintype "input"))
      (node (ref "D8") (pin "C") (pinfunction "C_+_C") (pintype "input"))
      (node (ref "FP1") (pin "2") (pinfunction "2_2") (pintype "passive"))
      (node (ref "U3") (pin "13") (pinfunction "VDDA_13") (pintype "power_in"))
      (node (ref "U4") (pin "11") (pinfunction "VDDIO_11") (pintype "power_in"))
      (node (ref "U4") (pin "3") (pinfunction "VDD_3") (pintype "power_in"))
    )
    (net (code "35") (name "5V") (class "Default")
      (node (ref "5V_PWR") (pin "A") (pinfunction "A_A") (pintype "passive"))
      (node (ref "C26") (pin "+") (pinfunction "+_+") (pintype "passive"))
      (node (ref "C33") (pin "1") (pinfunction "1_1") (pintype "passive"))
      (node (ref "C_IN") (pin "1") (pinfunction "1_1") (pintype "passive"))
      (node (ref "HC-05") (pin "5") (pinfunction "VIN_5") (pintype "power_in"))
      (node (ref "IC3") (pin "7") (pinfunction "VIN_7") (pintype "power_in"))
      (node (ref "MOTOR_LEFT") (pin "4") (pinfunction "4_4") (pintype "bidirectional"))
      (node (ref "MOTOR_RIGHT") (pin "4") (pinfunction "4_4") (pintype "bidirectional"))
      (node (ref "OLED") (pin "2") (pinfunction "VCC_2") (pintype "power_in"))
      (node (ref "R23") (pin "2") (pinfunction "2_2") (pintype "passive"))
      (node (ref "R_FBT") (pin "1") (pinfunction "1_1") (pintype "passive"))
      (node (ref "S1") (pin "4") (pinfunction "VOUT_4") (pintype "power_in"))
      (node (ref "S1") (pin "6") (pinfunction "VOS_6") (pintype "bidirectional"))
      (node (ref "TP_5V") (pin "P$1") (pinfunction "1_P$1") (pintype "bidirectional"))
      (node (ref "VR1") (pin "3") (pinfunction "VIN_3") (pintype "power_in"))
    )
    (net (code "36") (name "12V") (class "Default")
      (node (ref "C19") (pin "1") (pinfunction "1_1") (pintype "passive"))
      (node (ref "C2") (pin "1") (pinfunction "1_1") (pintype "passive"))
      (node (ref "C20") (pin "1") (pinfunction "1_1") (pintype "passive"))
      (node (ref "C22") (pin "1") (pinfunction "1_1") (pintype "passive"))
      (node (ref "C24") (pin "1") (pinfunction "1_1") (pintype "passive"))
      (node (ref "C3") (pin "1") (pinfunction "+_1") (pintype "passive"))
      (node (ref "IC2") (pin "14") (pinfunction "VOUT_14") (pintype "bidirectional"))
      (node (ref "IC2") (pin "15") (pinfunction "VOUT_15") (pintype "bidirectional"))
      (node (ref "IC2") (pin "16") (pinfunction "VOUT_16") (pintype "bidirectional"))
      (node (ref "R18") (pin "1") (pinfunction "1_1") (pintype "passive"))
      (node (ref "R22") (pin "2") (pinfunction "2_2") (pintype "passive"))
      (node (ref "TP_12V") (pin "P$1") (pinfunction "1_P$1") (pintype "bidirectional"))
      (node (ref "U1") (pin "13") (pinfunction "VM_13") (pintype "power_in"))
      (node (ref "U1") (pin "14") (pinfunction "VM_14") (pintype "power_in"))
      (node (ref "U1") (pin "24") (pinfunction "VM_24") (pintype "power_in"))
    )
    (net (code "37") (name "BOOT0") (class "Default")
      (node (ref "R34") (pin "2") (pinfunction "2_2") (pintype "passive"))
      (node (ref "U3") (pin "60") (pinfunction "BOOT0_60") (pintype "input"))
    )
    (net (code "38") (name "BOOT1") (class "Default")
      (node (ref "R33") (pin "1") (pinfunction "1_1") (pintype "passive"))
      (node (ref "U3") (pin "28") (pinfunction "PB2_28") (pintype "bidirectional"))
    )
    (net (code "39") (name "BTN_SEL") (class "Default")
      (node (ref "C30") (pin "1") (pinfunction "1_1") (pintype "passive"))
      (node (ref "R30") (pin "2") (pinfunction "2_2") (pintype "passive"))
      (node (ref "U3") (pin "54") (pinfunction "PD2_54") (pintype "bidirectional"))
    )
    (net (code "40") (name "BUZZER") (class "Default")
      (node (ref "Q3") (pin "1") (pinfunction "G_1") (pintype "passive"))
      (node (ref "R3") (pin "2") (pinfunction "2_2") (pintype "passive"))
      (node (ref "U3") (pin "44") (pinfunction "PA11_44") (pintype "bidirectional"))
    )
    (net (code "41") (name "FL_EMITTER") (class "Default")
      (node (ref "Q1") (pin "1") (pinfunction "G_1") (pintype "passive"))
      (node (ref "R8") (pin "2") (pinfunction "2_2") (pintype "passive"))
      (node (ref "U3") (pin "23") (pinfunction "PA7_23") (pintype "bidirectional"))
    )
    (net (code "42") (name "FL_RECEIVER") (class "Default")
      (node (ref "D5") (pin "E") (pinfunction "E_-_E") (pintype "output"))
      (node (ref "R1") (pin "2") (pinfunction "2_2") (pintype "passive"))
      (node (ref "U3") (pin "9") (pinfunction "PC1_9") (pintype "bidirectional"))
    )
    (net (code "43") (name "FR_EMITTER") (class "Default")
      (node (ref "Q2") (pin "1") (pinfunction "G_1") (pintype "passive"))
      (node (ref "R10") (pin "2") (pinfunction "2_2") (pintype "passive"))
      (node (ref "U3") (pin "26") (pinfunction "PB0_26") (pintype "bidirectional"))
    )
    (net (code "44") (name "FR_RECEIVER") (class "Default")
      (node (ref "D8") (pin "E") (pinfunction "E_-_E") (pintype "output"))
      (node (ref "R16") (pin "2") (pinfunction "2_2") (pintype "passive"))
      (node (ref "U3") (pin "10") (pinfunction "PC2_10") (pintype "bidirectional"))
    )
    (net (code "45") (name "GND") (class "Default")
      (node (ref "BOOT") (pin "5") (pinfunction "5_5") (pintype "passive"))
      (node (ref "BOOT") (pin "6") (pinfunction "6_6") (pintype "passive"))
      (node (ref "BTN_RST") (pin "1") (pinfunction "1_1") (pintype "bidirectional"))
      (node (ref "BTN_RST") (pin "2") (pinfunction "2_2") (pintype "bidirectional"))
      (node (ref "BTN_SEL") (pin "3") (pinfunction "3_3") (pintype "bidirectional"))
      (node (ref "BTN_SEL") (pin "4") (pinfunction "4_4") (pintype "bidirectional"))
      (node (ref "C10") (pin "2") (pinfunction "2_2") (pintype "passive"))
      (node (ref "C11") (pin "2") (pinfunction "2_2") (pintype "passive"))
      (node (ref "C12") (pin "2") (pinfunction "2_2") (pintype "passive"))
      (node (ref "C13") (pin "2") (pinfunction "2_2") (pintype "passive"))
      (node (ref "C26") (pin "-") (pinfunction "-_-") (pintype "passive"))
      (node (ref "C27") (pin "-") (pinfunction "-_-") (pintype "passive"))
      (node (ref "C30") (pin "2") (pinfunction "2_2") (pintype "passive"))
      (node (ref "C31") (pin "2") (pinfunction "2_2") (pintype "passive"))
      (node (ref "C32") (pin "2") (pinfunction "2_2") (pintype "passive"))
      (node (ref "C33") (pin "2") (pinfunction "2_2") (pintype "passive"))
      (node (ref "C36") (pin "2") (pinfunction "2_2") (pintype "passive"))
      (node (ref "C4") (pin "2") (pinfunction "2_2") (pintype "passive"))
      (node (ref "C42") (pin "2") (pinfunction "2_2") (pintype "passive"))
      (node (ref "C45") (pin "2") (pinfunction "2_2") (pintype "passive"))
      (node (ref "C46") (pin "2") (pinfunction "2_2") (pintype "passive"))
      (node (ref "C47") (pin "2") (pinfunction "2_2") (pintype "passive"))
      (node (ref "C48") (pin "2") (pinfunction "2_2") (pintype "passive"))
      (node (ref "C49") (pin "2") (pinfunction "2_2") (pintype "passive"))
      (node (ref "C5") (pin "2") (pinfunction "2_2") (pintype "passive"))
      (node (ref "C50") (pin "2") (pinfunction "2_2") (pintype "passive"))
      (node (ref "C51") (pin "2") (pinfunction "2_2") (pintype "passive"))
      (node (ref "C6") (pin "2") (pinfunction "2_2") (pintype "passive"))
      (node (ref "C7") (pin "2") (pinfunction "2_2") (pintype "passive"))
      (node (ref "C8") (pin "2") (pinfunction "2_2") (pintype "passive"))
      (node (ref "C9") (pin "2") (pinfunction "2_2") (pintype "passive"))
      (node (ref "C_IN") (pin "2") (pinfunction "2_2") (pintype "passive"))
      (node (ref "C_OUT") (pin "2") (pinfunction "2_2") (pintype "passive"))
      (node (ref "C_VC") (pin "2") (pinfunction "2_2") (pintype "passive"))
      (node (ref "DEBUG") (pin "3") (pinfunction "3_3") (pintype "passive"))
      (node (ref "DEBUG") (pin "4") (pinfunction "4_4") (pintype "passive"))
      (node (ref "FP2") (pin "1") (pinfunction "1_1") (pintype "passive"))
      (node (ref "HC-05") (pin "4") (pinfunction "GND_4") (pintype "power_in"))
      (node (ref "IC3") (pin "4") (pinfunction "SGND_4") (pintype "power_in"))
      (node (ref "IC3") (pin "6") (pinfunction "PGND_6") (pintype "power_in"))
      (node (ref "IC3") (pin "9") (pinfunction "EP_9") (pintype "power_in"))
      (node (ref "MOTOR_LEFT") (pin "3") (pinfunction "3_3") (pintype "bidirectional"))
      (node (ref "MOTOR_RIGHT") (pin "3") (pinfunction "3_3") (pintype "bidirectional"))
      (node (ref "OLED") (pin "1") (pinfunction "GND_1") (pintype "power_in"))
      (node (ref "Q1") (pin "2") (pinfunction "S_2") (pintype "passive"))
      (node (ref "Q2") (pin "2") (pinfunction "S_2") (pintype "passive"))
      (node (ref "Q3") (pin "2") (pinfunction "S_2") (pintype "passive"))
      (node (ref "Q4") (pin "2") (pinfunction "S_2") (pintype "passive"))
      (node (ref "Q5") (pin "2") (pinfunction "S_2") (pintype "passive"))
      (node (ref "R10") (pin "1") (pinfunction "1_1") (pintype "passive"))
      (node (ref "R11") (pin "1") (pinfunction "1_1") (pintype "passive"))
      (node (ref "R14") (pin "1") (pinfunction "1_1") (pintype "passive"))
      (node (ref "R15") (pin "1") (pinfunction "1_1") (pintype "passive"))
      (node (ref "R25") (pin "1") (pinfunction "1_1") (pintype "passive"))
      (node (ref "R27") (pin "1") (pinfunction "1_1") (pintype "passive"))
      (node (ref "R3") (pin "1") (pinfunction "1_1") (pintype "passive"))
      (node (ref "R31") (pin "1") (pinfunction "1_1") (pintype "passive"))
      (node (ref "R4") (pin "1") (pinfunction "1_1") (pintype "passive"))
      (node (ref "R5") (pin "1") (pinfunction "1_1") (pintype "passive"))
      (node (ref "R8") (pin "1") (pinfunction "1_1") (pintype "passive"))
      (node (ref "RB") (pin "1") (pinfunction "1_1") (pintype "passive"))
      (node (ref "R_FBB") (pin "1") (pinfunction "1_1") (pintype "passive"))
      (node (ref "S1") (pin "10") (pinfunction "GND_10") (pintype "power_in"))
      (node (ref "S1") (pin "5") (pinfunction "GND_5") (pintype "power_in"))
      (node (ref "S1") (pin "9") (pinfunction "GND_9") (pintype "power_in"))
      (node (ref "U$10") (pin "1") (pinfunction "1_1") (pintype "bidirectional"))
      (node (ref "U$6") (pin "2") (pinfunction "2_2") (pintype "bidirectional"))
      (node (ref "U$7") (pin "2") (pinfunction "2_2") (pintype "bidirectional"))
      (node (ref "U3") (pin "18") (pinfunction "VSS_4_18") (pintype "power_in"))
      (node (ref "U3") (pin "63") (pinfunction "VSS_3_63") (pintype "power_in"))
      (node (ref "VR1") (pin "1") (pinfunction "GND_1") (pintype "power_in"))
    )
    (net (code "46") (name "GND_A") (class "Default")
      (node (ref "C28") (pin "2") (pinfunction "2_2") (pintype "passive"))
      (node (ref "C29") (pin "2") (pinfunction "2_2") (pintype "passive"))
      (node (ref "C34") (pin "2") (pinfunction "2_2") (pintype "passive"))
      (node (ref "C35") (pin "2") (pinfunction "2_2") (pintype "passive"))
      (node (ref "C43") (pin "2") (pinfunction "2_2") (pintype "passive"))
      (node (ref "C44") (pin "2") (pinfunction "2_2") (pintype "passive"))
      (node (ref "FP2") (pin "2") (pinfunction "2_2") (pintype "passive"))
      (node (ref "R1") (pin "1") (pinfunction "1_1") (pintype "passive"))
      (node (ref "R13") (pin "1") (pinfunction "1_1") (pintype "passive"))
      (node (ref "R16") (pin "1") (pinfunction "1_1") (pintype "passive"))
      (node (ref "R2") (pin "1") (pinfunction "1_1") (pintype "passive"))
      (node (ref "U3") (pin "12") (pinfunction "VSSA_12") (pintype "power_in"))
      (node (ref "U4") (pin "4") (pinfunction "GNDA_4") (pintype "power_in"))
      (node (ref "U4") (pin "6") (pinfunction "GNDIO_6") (pintype "power_in"))
      (node (ref "U4") (pin "7") (pinfunction "PS_7") (pintype "input"))
    )
    (net (code "47") (name "GND_M") (class "Default")
      (node (ref "C1") (pin "2") (pinfunction "2_2") (pintype "passive"))
      (node (ref "C2") (pin "2") (pinfunction "2_2") (pintype "passive"))
      (node (ref "C3") (pin "2") (pinfunction "-_2") (pintype "passive"))
      (node (ref "U$6") (pin "1") (pinfunction "1_1") (pintype "bidirectional"))
      (node (ref "U1") (pin "10") (pinfunction "M_GND2_10") (pintype "power_in"))
      (node (ref "U1") (pin "18") (pinfunction "GND_18") (pintype "power_in"))
      (node (ref "U1") (pin "3") (pinfunction "M_GND1_3") (pintype "power_in"))
      (node (ref "U1") (pin "4") (pinfunction "M_GND1_4") (pintype "power_in"))
      (node (ref "U1") (pin "9") (pinfunction "M_GND2_9") (pintype "power_in"))
    )
    (net (code "48") (name "GND_SW") (class "Default")
      (node (ref "C15") (pin "2") (pinfunction "2_2") (pintype "passive"))
      (node (ref "C16") (pin "2") (pinfunction "2_2") (pintype "passive"))
      (node (ref "C17") (pin "2") (pinfunction "2_2") (pintype "passive"))
      (node (ref "C18") (pin "2") (pinfunction "2_2") (pintype "passive"))
      (node (ref "C19") (pin "2") (pinfunction "2_2") (pintype "passive"))
      (node (ref "C20") (pin "2") (pinfunction "2_2") (pintype "passive"))
      (node (ref "C21") (pin "2") (pinfunction "2_2") (pintype "passive"))
      (node (ref "C22") (pin "2") (pinfunction "2_2") (pintype "passive"))
      (node (ref "C23") (pin "2") (pinfunction "2_2") (pintype "passive"))
      (node (ref "C24") (pin "2") (pinfunction "2_2") (pintype "passive"))
      (node (ref "C25") (pin "2") (pinfunction "2_2") (pintype "passive"))
      (node (ref "IC2") (pin "11") (pinfunction "NC_11") (pintype "bidirectional"))
      (node (ref "IC2") (pin "12") (pinfunction "NC_12") (pintype "bidirectional"))
      (node (ref "IC2") (pin "13") (pinfunction "MODE_13") (pintype "bidirectional"))
      (node (ref "IC2") (pin "20") (pinfunction "AGND_20") (pintype "bidirectional"))
      (node (ref "IC2") (pin "21") (pinfunction "PGND_21") (pintype "bidirectional"))
      (node (ref "R19") (pin "2") (pinfunction "2_2") (pintype "passive"))
      (node (ref "R21") (pin "2") (pinfunction "2_2") (pintype "passive"))
      (node (ref "R24") (pin "1") (pinfunction "1_1") (pintype "passive"))
      (node (ref "U$7") (pin "1") (pinfunction "1_1") (pintype "bidirectional"))
    )
    (net (code "49") (name "LED_B") (class "Default")
      (node (ref "LED_B") (pin "A") (pinfunction "A_A") (pintype "passive"))
      (node (ref "U3") (pin "50") (pinfunction "PA15_50") (pintype "bidirectional"))
    )
    (net (code "50") (name "LED_G") (class "Default")
      (node (ref "LED_G") (pin "A") (pinfunction "A_A") (pintype "passive"))
      (node (ref "U3") (pin "51") (pinfunction "PC10_51") (pintype "bidirectional"))
    )
    (net (code "51") (name "LED_R") (class "Default")
      (node (ref "LED_R") (pin "A") (pinfunction "A_A") (pintype "passive"))
      (node (ref "U3") (pin "52") (pinfunction "PC11_52") (pintype "bidirectional"))
    )
    (net (code "52") (name "L_EMITTER") (class "Default")
      (node (ref "Q4") (pin "1") (pinfunction "G_1") (pintype "passive"))
      (node (ref "R11") (pin "2") (pinfunction "2_2") (pintype "passive"))
      (node (ref "U3") (pin "22") (pinfunction "PA6_22") (pintype "bidirectional"))
    )
    (net (code "53") (name "L_RECEIVER") (class "Default")
      (node (ref "D4") (pin "E") (pinfunction "E_-_E") (pintype "output"))
      (node (ref "R13") (pin "2") (pinfunction "2_2") (pintype "passive"))
      (node (ref "U3") (pin "8") (pinfunction "PC0_8") (pintype "bidirectional"))
    )
    (net (code "54") (name "Net-(5V_PWR-K)") (class "Default")
      (node (ref "5V_PWR") (pin "C") (pinfunction "K_C") (pintype "passive"))
      (node (ref "R25") (pin "2") (pinfunction "2_2") (pintype "passive"))
    )
    (net (code "55") (name "Net-(BOOT-Pad3)") (class "Default")
      (node (ref "BOOT") (pin "3") (pinfunction "3_3") (pintype "passive"))
      (node (ref "R34") (pin "1") (pinfunction "1_1") (pintype "passive"))
    )
    (net (code "56") (name "Net-(BOOT-Pad4)") (class "Default")
      (node (ref "BOOT") (pin "4") (pinfunction "4_4") (pintype "passive"))
      (node (ref "R33") (pin "2") (pinfunction "2_2") (pintype "passive"))
    )
    (net (code "57") (name "Net-(BTN_SEL-Pad1)") (class "Default")
      (node (ref "BTN_SEL") (pin "1") (pinfunction "1_1") (pintype "bidirectional"))
      (node (ref "BTN_SEL") (pin "2") (pinfunction "2_2") (pintype "bidirectional"))
      (node (ref "R29") (pin "2") (pinfunction "2_2") (pintype "passive"))
      (node (ref "R30") (pin "1") (pinfunction "1_1") (pintype "passive"))
    )
    (net (code "58") (name "Net-(C14-Pad1)") (class "Default")
      (node (ref "C14") (pin "1") (pinfunction "1_1") (pintype "passive"))
      (node (ref "IC2") (pin "4") (pinfunction "SW_4") (pintype "bidirectional"))
      (node (ref "IC2") (pin "5") (pinfunction "SW_5") (pintype "bidirectional"))
      (node (ref "IC2") (pin "6") (pinfunction "SW_6") (pintype "bidirectional"))
      (node (ref "IC2") (pin "7") (pinfunction "SW_7") (pintype "bidirectional"))
      (node (ref "L1") (pin "2") (pinfunction "2_2") (pintype "bidirectional"))
      (node (ref "R17") (pin "1") (pinfunction "1_1") (pintype "passive"))
    )
    (net (code "59") (name "Net-(C23-Pad1)") (class "Default")
      (node (ref "C23") (pin "1") (pinfunction "1_1") (pintype "passive"))
      (node (ref "R20") (pin "2") (pinfunction "2_2") (pintype "passive"))
    )
    (net (code "60") (name "Net-(FL_EMITTER--_CATHODE)") (class "Default")
      (node (ref "FL_EMITTER") (pin "-") (pinfunction "-_CATHODE_-") (pintype "passive"))
      (node (ref "R6") (pin "2") (pinfunction "2_2") (pintype "passive"))
    )
    (net (code "61") (name "Net-(FR_EMITTER--_CATHODE)") (class "Default")
      (node (ref "FR_EMITTER") (pin "-") (pinfunction "-_CATHODE_-") (pintype "passive"))
      (node (ref "R9") (pin "2") (pinfunction "2_2") (pintype "passive"))
    )
    (net (code "62") (name "Net-(IC2-BOOT)") (class "Default")
      (node (ref "C14") (pin "2") (pinfunction "2_2") (pintype "passive"))
      (node (ref "IC2") (pin "8") (pinfunction "BOOT_8") (pintype "bidirectional"))
    )
    (net (code "63") (name "Net-(IC2-COMP)") (class "Default")
      (node (ref "C21") (pin "1") (pinfunction "1_1") (pintype "passive"))
      (node (ref "IC2") (pin "18") (pinfunction "COMP_18") (pintype "bidirectional"))
      (node (ref "R20") (pin "1") (pinfunction "1_1") (pintype "passive"))
    )
    (net (code "64") (name "Net-(IC2-EN)") (class "Default")
      (node (ref "C15") (pin "1") (pinfunction "1_1") (pintype "passive"))
      (node (ref "IC2") (pin "1") (pinfunction "VCC_1") (pintype "bidirectional"))
      (node (ref "IC2") (pin "2") (pinfunction "EN_2") (pintype "bidirectional"))
    )
    (net (code "65") (name "Net-(IC2-FB)") (class "Default")
      (node (ref "IC2") (pin "17") (pinfunction "FB_17") (pintype "bidirectional"))
      (node (ref "R18") (pin "2") (pinfunction "2_2") (pintype "passive"))
      (node (ref "R19") (pin "1") (pinfunction "1_1") (pintype "passive"))
    )
    (net (code "66") (name "Net-(IC2-FSW)") (class "Default")
      (node (ref "IC2") (pin "3") (pinfunction "FSW_3") (pintype "bidirectional"))
      (node (ref "R17") (pin "2") (pinfunction "2_2") (pintype "passive"))
    )
    (net (code "67") (name "Net-(IC2-ILIM)") (class "Default")
      (node (ref "IC2") (pin "19") (pinfunction "ILIM_19") (pintype "bidirectional"))
      (node (ref "R21") (pin "1") (pinfunction "1_1") (pintype "passive"))
    )
    (net (code "68") (name "Net-(IC2-SS)") (class "Default")
      (node (ref "C18") (pin "1") (pinfunction "1_1") (pintype "passive"))
      (node (ref "IC2") (pin "10") (pinfunction "SS_10") (pintype "bidirectional"))
    )
    (net (code "69") (name "Net-(IC3-VCON)") (class "Default")
      (node (ref "C_VC") (pin "1") (pinfunction "1_1") (pintype "passive"))
      (node (ref "IC3") (pin "2") (pinfunction "VCON_2") (pintype "bidirectional"))
      (node (ref "RB") (pin "2") (pinfunction "2_2") (pintype "passive"))
      (node (ref "RT") (pin "1") (pinfunction "1_1") (pintype "passive"))
    )
    (net (code "70") (name "Net-(IC3-VREF)") (class "Default")
      (node (ref "IC3") (pin "8") (pinfunction "VREF_8") (pintype "input"))
      (node (ref "RT") (pin "2") (pinfunction "2_2") (pintype "passive"))
    )
    (net (code "71") (name "Net-(LED_B-K)") (class "Default")
      (node (ref "LED_B") (pin "C") (pinfunction "K_C") (pintype "passive"))
      (node (ref "R5") (pin "2") (pinfunction "2_2") (pintype "passive"))
    )
    (net (code "72") (name "Net-(LED_G-K)") (class "Default")
      (node (ref "LED_G") (pin "C") (pinfunction "K_C") (pintype "passive"))
      (node (ref "R4") (pin "2") (pinfunction "2_2") (pintype "passive"))
    )
    (net (code "73") (name "Net-(LED_R-K)") (class "Default")
      (node (ref "LED_R") (pin "C") (pinfunction "K_C") (pintype "passive"))
      (node (ref "R14") (pin "2") (pinfunction "2_2") (pintype "passive"))
    )
    (net (code "74") (name "Net-(L_EMITTER--_CATHODE)") (class "Default")
      (node (ref "L_EMITTER") (pin "-") (pinfunction "-_CATHODE_-") (pintype "passive"))
      (node (ref "R7") (pin "2") (pinfunction "2_2") (pintype "passive"))
    )
    (net (code "75") (name "Net-(Q1-D)") (class "Default")
      (node (ref "Q1") (pin "3") (pinfunction "D_3") (pintype "passive"))
      (node (ref "R6") (pin "1") (pinfunction "1_1") (pintype "passive"))
    )
    (net (code "76") (name "Net-(Q2-D)") (class "Default")
      (node (ref "Q2") (pin "3") (pinfunction "D_3") (pintype "passive"))
      (node (ref "R9") (pin "1") (pinfunction "1_1") (pintype "passive"))
    )
    (net (code "77") (name "Net-(Q3-D)") (class "Default")
      (node (ref "Q3") (pin "3") (pinfunction "D_3") (pintype "passive"))
      (node (ref "U$1") (pin "-") (pinfunction "-_CATHODE_-") (pintype "passive"))
      (node (ref "U$4") (pin "-") (pinfunction "-_-") (pintype "bidirectional"))
    )
    (net (code "78") (name "Net-(Q4-D)") (class "Default")
      (node (ref "Q4") (pin "3") (pinfunction "D_3") (pintype "passive"))
      (node (ref "R7") (pin "1") (pinfunction "1_1") (pintype "passive"))
    )
    (net (code "79") (name "Net-(Q5-D)") (class "Default")
      (node (ref "Q5") (pin "3") (pinfunction "D_3") (pintype "passive"))
      (node (ref "R12") (pin "1") (pinfunction "1_1") (pintype "passive"))
    )
    (net (code "80") (name "Net-(R26-Pad2)") (class "Default")
      (node (ref "R26") (pin "2") (pinfunction "2_2") (pintype "passive"))
      (node (ref "U$10") (pin "2") (pinfunction "2_2") (pintype "bidirectional"))
    )
    (net (code "81") (name "Net-(R_EMITTER--_CATHODE)") (class "Default")
      (node (ref "R12") (pin "2") (pinfunction "2_2") (pintype "passive"))
      (node (ref "R_EMITTER") (pin "-") (pinfunction "-_CATHODE_-") (pintype "passive"))
    )
    (net (code "82") (name "Net-(S1-FB)") (class "Default")
      (node (ref "R_FBB") (pin "2") (pinfunction "2_2") (pintype "passive"))
      (node (ref "R_FBT") (pin "2") (pinfunction "2_2") (pintype "passive"))
      (node (ref "S1") (pin "2") (pinfunction "FB_2") (pintype "bidirectional"))
    )
    (net (code "83") (name "Net-(S1-PG)") (class "Default")
      (node (ref "R23") (pin "1") (pinfunction "1_1") (pintype "passive"))
      (node (ref "S1") (pin "3") (pinfunction "PG_3") (pintype "bidirectional"))
    )
    (net (code "84") (name "Net-(S1-SS)") (class "Default")
      (node (ref "C31") (pin "1") (pinfunction "1_1") (pintype "passive"))
      (node (ref "S1") (pin "1") (pinfunction "SS_1") (pintype "bidirectional"))
    )
    (net (code "85") (name "Net-(SW-COM)") (class "Default")
      (node (ref "R28") (pin "2") (pinfunction "2_2") (pintype "passive"))
      (node (ref "SW") (pin "1") (pinfunction "1_1") (pintype "bidirectional"))
      (node (ref "SW") (pin "2_COM") (pinfunction "COM_2_COM") (pintype "bidirectional"))
      (node (ref "U$10") (pin "3") (pinfunction "3_3") (pintype "bidirectional"))
    )
    (net (code "86") (name "Net-(U3-VCAP_1)") (class "Default")
      (node (ref "C45") (pin "1") (pinfunction "1_1") (pintype "passive"))
      (node (ref "U3") (pin "31") (pinfunction "VCAP_1_31") (pintype "power_in"))
    )
    (net (code "87") (name "Net-(U3-VCAP_2)") (class "Default")
      (node (ref "C46") (pin "1") (pinfunction "1_1") (pintype "passive"))
      (node (ref "U3") (pin "47") (pinfunction "VCAP_2_47") (pintype "power_in"))
    )
    (net (code "88") (name "RESET") (class "Default")
      (node (ref "BTN_RST") (pin "3") (pinfunction "3_3") (pintype "bidirectional"))
      (node (ref "BTN_RST") (pin "4") (pinfunction "4_4") (pintype "bidirectional"))
      (node (ref "C36") (pin "1") (pinfunction "1_1") (pintype "passive"))
      (node (ref "U3") (pin "7") (pinfunction "NRST_7") (pintype "bidirectional"))
    )
    (net (code "89") (name "R_EMITTER") (class "Default")
      (node (ref "Q5") (pin "1") (pinfunction "G_1") (pintype "passive"))
      (node (ref "R15") (pin "2") (pinfunction "2_2") (pintype "passive"))
      (node (ref "U3") (pin "27") (pinfunction "PB1_27") (pintype "bidirectional"))
    )
    (net (code "90") (name "R_RECEIVER") (class "Default")
      (node (ref "D6") (pin "E") (pinfunction "E_-_E") (pintype "output"))
      (node (ref "R2") (pin "2") (pinfunction "2_2") (pintype "passive"))
      (node (ref "U3") (pin "11") (pinfunction "PC3_11") (pintype "bidirectional"))
    )
    (net (code "91") (name "VOLTM_BATT") (class "Default")
      (node (ref "R28") (pin "1") (pinfunction "1_1") (pintype "passive"))
      (node (ref "R31") (pin "2") (pinfunction "2_2") (pintype "passive"))
      (node (ref "U3") (pin "17") (pinfunction "PA3_17") (pintype "bidirectional"))
    )
    (net (code "92") (name "VOLTM_BOOST") (class "Default")
      (node (ref "R22") (pin "1") (pinfunction "1_1") (pintype "passive"))
      (node (ref "R24") (pin "2") (pinfunction "2_2") (pintype "passive"))
      (node (ref "U3") (pin "16") (pinfunction "PA2_16") (pintype "bidirectional"))
    )
    (net (code "93") (name "VOLTM_CELL1") (class "Default")
      (node (ref "R26") (pin "1") (pinfunction "1_1") (pintype "passive"))
      (node (ref "R27") (pin "2") (pinfunction "2_2") (pintype "passive"))
      (node (ref "U3") (pin "20") (pinfunction "PA4_20") (pintype "bidirectional"))
    )
    (net (code "94") (name "V_BAT") (class "Default")
      (node (ref "C16") (pin "1") (pinfunction "1_1") (pintype "passive"))
      (node (ref "C17") (pin "1") (pinfunction "1_1") (pintype "passive"))
      (node (ref "C25") (pin "1") (pinfunction "1_1") (pintype "passive"))
      (node (ref "C32") (pin "1") (pinfunction "1_1") (pintype "passive"))
      (node (ref "IC2") (pin "9") (pinfunction "VIN_9") (pintype "bidirectional"))
      (node (ref "L1") (pin "1") (pinfunction "1_1") (pintype "bidirectional"))
      (node (ref "S1") (pin "7") (pinfunction "EN_7") (pintype "bidirectional"))
      (node (ref "S1") (pin "8") (pinfunction "VIN_8") (pintype "power_in"))
      (node (ref "SW") (pin "3") (pinfunction "3_3") (pintype "bidirectional"))
    )
    (net (code "95") (name "unconnected-(HC-05-EN-Pad6)") (class "Default")
      (node (ref "HC-05") (pin "6") (pinfunction "EN_6") (pintype "bidirectional"))
    )
    (net (code "96") (name "unconnected-(HC-05-STATE-Pad1)") (class "Default")
      (node (ref "HC-05") (pin "1") (pinfunction "STATE_1") (pintype "bidirectional"))
    )
    (net (code "97") (name "unconnected-(IC3-EN-Pad1)") (class "Default")
      (node (ref "IC3") (pin "1") (pinfunction "EN_1") (pintype "bidirectional"))
    )
    (net (code "98") (name "unconnected-(U3-PA12-Pad45)") (class "Default")
      (node (ref "U3") (pin "45") (pinfunction "PA12_45") (pintype "bidirectional"))
    )
    (net (code "99") (name "unconnected-(U3-PB11-Pad30)") (class "Default")
      (node (ref "U3") (pin "30") (pinfunction "PB11_30") (pintype "bidirectional"))
    )
    (net (code "100") (name "unconnected-(U3-PC6-Pad37)") (class "Default")
      (node (ref "U3") (pin "37") (pinfunction "PC6_37") (pintype "bidirectional"))
    )
    (net (code "101") (name "unconnected-(U3-PC7-Pad38)") (class "Default")
      (node (ref "U3") (pin "38") (pinfunction "PC7_38") (pintype "bidirectional"))
    )
    (net (code "102") (name "unconnected-(U3-PC8-Pad39)") (class "Default")
      (node (ref "U3") (pin "39") (pinfunction "PC8_39") (pintype "bidirectional"))
    )
    (net (code "103") (name "unconnected-(U3-PC12-Pad53)") (class "Default")
      (node (ref "U3") (pin "53") (pinfunction "PC12_53") (pintype "bidirectional"))
    )
    (net (code "104") (name "unconnected-(U3-PC13-TAMPER-RTC-Pad2)") (class "Default")
      (node (ref "U3") (pin "2") (pinfunction "PC13-TAMPER-RTC_2") (pintype "bidirectional"))
    )
    (net (code "105") (name "unconnected-(U3-PC14-OSC32_IN-Pad3)") (class "Default")
      (node (ref "U3") (pin "3") (pinfunction "PC14-OSC32_IN_3") (pintype "bidirectional"))
    )
    (net (code "106") (name "unconnected-(U3-PC15-OSC32_OUT-Pad4)") (class "Default")
      (node (ref "U3") (pin "4") (pinfunction "PC15-OSC32_OUT_4") (pintype "bidirectional"))
    )
    (net (code "107") (name "unconnected-(U3-PH0_OSC_IN-Pad5)") (class "Default")
      (node (ref "U3") (pin "5") (pinfunction "PH0_OSC_IN_5") (pintype "input"))
    )
    (net (code "108") (name "unconnected-(U3-PH1_OSC_OUT-Pad6)") (class "Default")
      (node (ref "U3") (pin "6") (pinfunction "PH1_OSC_OUT_6") (pintype "output"))
    )
    (net (code "109") (name "unconnected-(U4-INT2-Pad1)") (class "Default")
      (node (ref "U4") (pin "1") (pinfunction "INT2_1") (pintype "bidirectional"))
    )
    (net (code "110") (name "unconnected-(U4-INT4-Pad13)") (class "Default")
      (node (ref "U4") (pin "13") (pinfunction "INT4_13") (pintype "bidirectional"))
    )
  )
)
